# design.net
KiCad netlist of a schematic drawn in Altium Designer
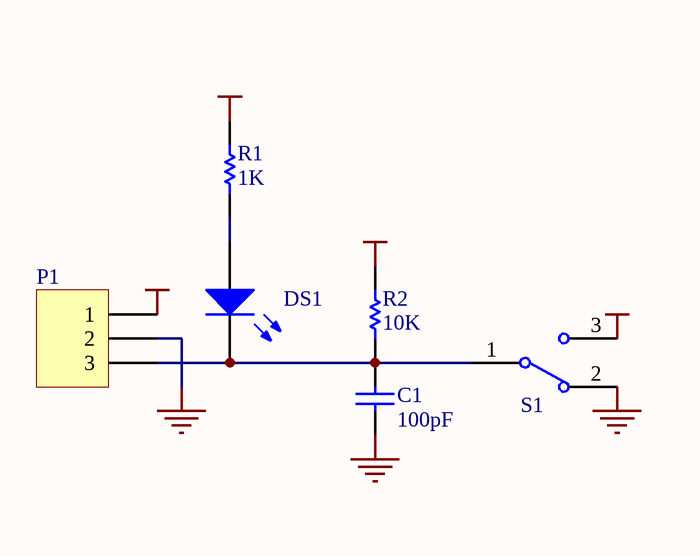
[diagram p0: 極限開關.SCHDOC]

(export (version "E")
  (design (tool "Eeschema 10.0.6"))
  (components
    (comp (ref "C1")
      (value "100pF")
      (footprint "0805")
      (description "Capacitor")
      (fields (field (name "Comment") "Cap") (field (name "PUBLISHER") "Altium Limited"))
      (libsource (lib "Miscellaneous Devices") (part "Cap"))
    )
    (comp (ref "DS1")
      (value "LED3")
      (footprint "SMD _LED")
      (description "Typical BLUE SiC LED")
      (fields (field (name "PUBLISHER") "Altium Limited"))
      (libsource (lib "Miscellaneous Devices") (part "LED3"))
    )
    (comp (ref "P1")
      (value "Header 3")
      (footprint "2mm 3pin")
      (description "Header, 3-Pin")
      (fields (field (name "PUBLISHER") "Altium Limited"))
      (libsource (lib "Miscellaneous Connectors") (part "Header 3"))
    )
    (comp (ref "R1")
      (value "1K")
      (footprint "0805")
      (description "Resistor")
      (fields (field (name "Comment") "Res1") (field (name "PUBLISHER") "Altium Limited"))
      (libsource (lib "Miscellaneous Devices") (part "Res1"))
    )
    (comp (ref "R2")
      (value "10K")
      (footprint "0805")
      (description "Resistor")
      (fields (field (name "Comment") "Res1") (field (name "PUBLISHER") "Altium Limited"))
      (libsource (lib "Miscellaneous Devices") (part "Res1"))
    )
    (comp (ref "S1")
      (value "switch")
      (footprint "mydata:switch")
      (description "SPDT Subminiature Toggle Switch, Right Angle Mounting, Vertical Actuation")
      (fields (field (name "PUBLISHER") "Altium Limited"))
      (libsource (lib "mydata") (part "switch"))
    )
  )
  (nets
    (net (code "1") (name "GND") (class "Default")
      (node (ref "C1") (pin "1") (pinfunction "1_1") (pintype "passive"))
      (node (ref "P1") (pin "2") (pinfunction "2_2") (pintype "passive"))
      (node (ref "S1") (pin "2") (pintype "passive"))
    )
    (net (code "2") (name "Net-(DS1-A)") (class "Default")
      (node (ref "DS1") (pin "1") (pinfunction "A_1") (pintype "passive"))
      (node (ref "R1") (pin "1") (pinfunction "1_1") (pintype "passive"))
    )
    (net (code "3") (name "Net-(DS1-K)") (class "Default")
      (node (ref "C1") (pin "2") (pinfunction "2_2") (pintype "passive"))
      (node (ref "DS1") (pin "2") (pinfunction "K_2") (pintype "passive"))
      (node (ref "P1") (pin "3") (pinfunction "3_3") (pintype "passive"))
      (node (ref "R2") (pin "1") (pinfunction "1_1") (pintype "passive"))
      (node (ref "S1") (pin "1") (pintype "passive"))
    )
    (net (code "4") (name "VCC") (class "Default")
      (node (ref "P1") (pin "1") (pinfunction "1_1") (pintype "passive"))
      (node (ref "R1") (pin "2") (pinfunction "2_2") (pintype "passive"))
      (node (ref "R2") (pin "2") (pinfunction "2_2") (pintype "passive"))
      (node (ref "S1") (pin "3") (pintype "passive"))
    )
  )
)
